# led_driver_v1_1.net
KiCad netlist of a schematic drawn in EAGLE
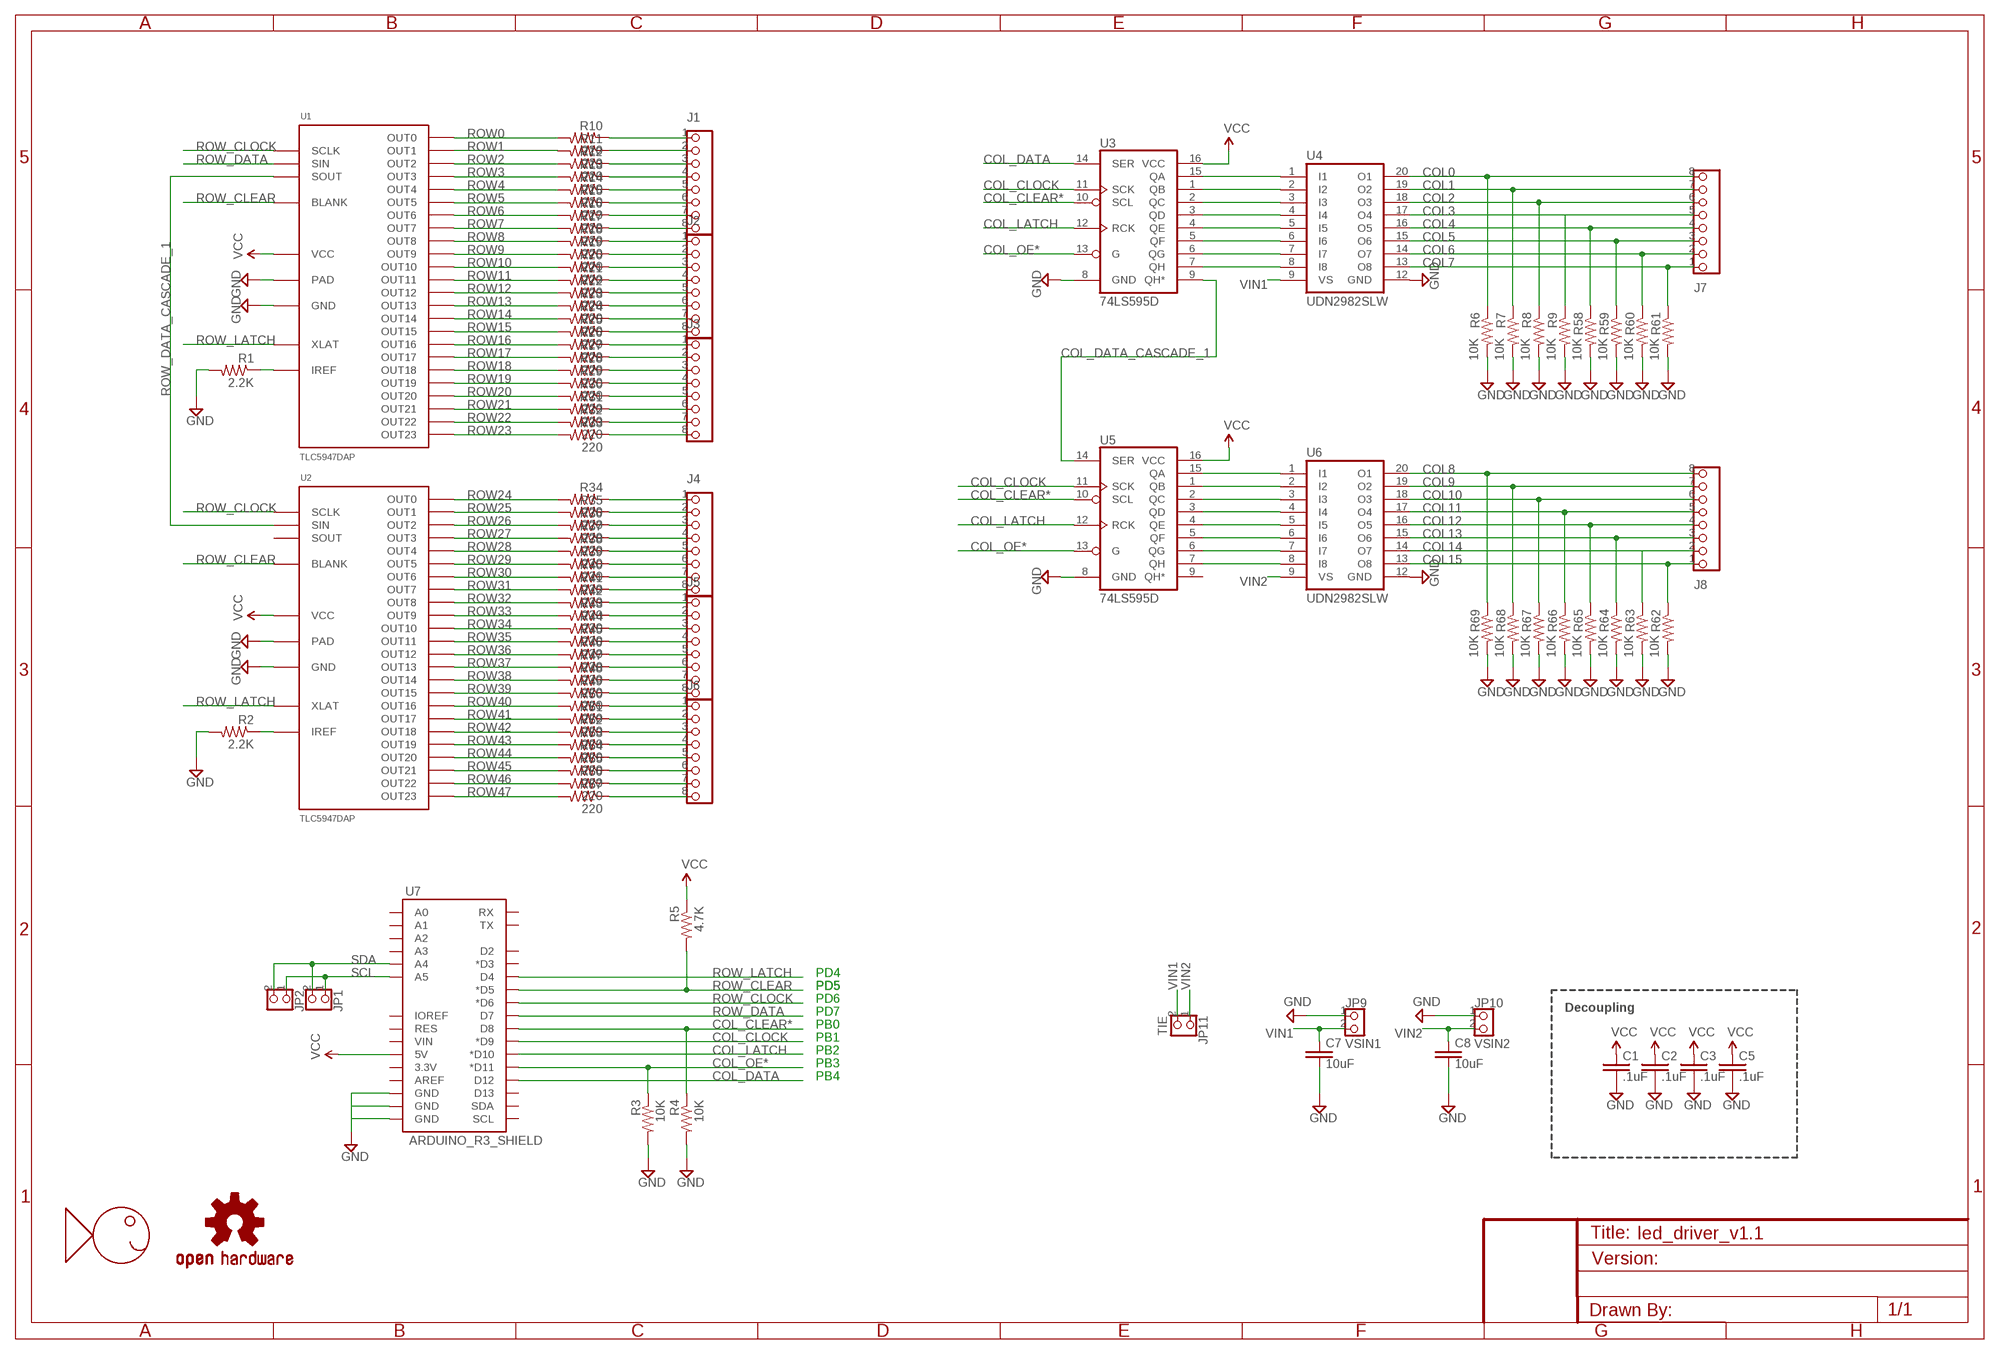
[diagram p0: schematic, sheet 1]

(export (version "E")
  (design (tool "Eeschema 10.0.6"))
  (components
    (comp (ref "C1")
      (value ".1uF")
      (footprint "eagle-import:C0603")
      (libsource (lib "eagle-import") (part "CAPACITORC0603"))
    )
    (comp (ref "C2")
      (value ".1uF")
      (footprint "eagle-import:C0603")
      (libsource (lib "eagle-import") (part "CAPACITORC0603"))
    )
    (comp (ref "C3")
      (value ".1uF")
      (footprint "eagle-import:C0603")
      (libsource (lib "eagle-import") (part "CAPACITORC0603"))
    )
    (comp (ref "C5")
      (value ".1uF")
      (footprint "eagle-import:C0603")
      (libsource (lib "eagle-import") (part "CAPACITORC0603"))
    )
    (comp (ref "C7")
      (value "10uF")
      (footprint "eagle-import:C0603")
      (libsource (lib "eagle-import") (part "CAPACITORC0603"))
    )
    (comp (ref "C8")
      (value "10uF")
      (footprint "eagle-import:C0603")
      (libsource (lib "eagle-import") (part "CAPACITORC0603"))
    )
    (comp (ref "J1")
      (value "PINHD-1X8")
      (footprint "eagle-import:1X08")
      (libsource (lib "eagle-import") (part "PINHD-1X8"))
    )
    (comp (ref "J2")
      (value "PINHD-1X8")
      (footprint "eagle-import:1X08")
      (libsource (lib "eagle-import") (part "PINHD-1X8"))
    )
    (comp (ref "J3")
      (value "PINHD-1X8")
      (footprint "eagle-import:1X08")
      (libsource (lib "eagle-import") (part "PINHD-1X8"))
    )
    (comp (ref "J4")
      (value "PINHD-1X8")
      (footprint "eagle-import:1X08")
      (libsource (lib "eagle-import") (part "PINHD-1X8"))
    )
    (comp (ref "J5")
      (value "PINHD-1X8")
      (footprint "eagle-import:1X08")
      (libsource (lib "eagle-import") (part "PINHD-1X8"))
    )
    (comp (ref "J6")
      (value "PINHD-1X8")
      (footprint "eagle-import:1X08")
      (libsource (lib "eagle-import") (part "PINHD-1X8"))
    )
    (comp (ref "J7")
      (value "PINHD-1X8")
      (footprint "eagle-import:1X08")
      (libsource (lib "eagle-import") (part "PINHD-1X8"))
    )
    (comp (ref "J8")
      (value "PINHD-1X8")
      (footprint "eagle-import:1X08")
      (libsource (lib "eagle-import") (part "PINHD-1X8"))
    )
    (comp (ref "JP1")
      (value "PINHD-1X2")
      (footprint "eagle-import:1X02")
      (libsource (lib "eagle-import") (part "PINHD-1X2"))
    )
    (comp (ref "JP2")
      (value "PINHD-1X2")
      (footprint "eagle-import:1X02")
      (libsource (lib "eagle-import") (part "PINHD-1X2"))
    )
    (comp (ref "JP9")
      (value "VSIN1")
      (footprint "eagle-import:1X02")
      (libsource (lib "eagle-import") (part "PINHD-1X2"))
    )
    (comp (ref "JP10")
      (value "VSIN2")
      (footprint "eagle-import:1X02")
      (libsource (lib "eagle-import") (part "PINHD-1X2"))
    )
    (comp (ref "JP11")
      (value "TIE")
      (footprint "eagle-import:1X02")
      (libsource (lib "eagle-import") (part "PINHD-1X2"))
    )
    (comp (ref "LOGO1")
      (value "OSHW-LOGOS")
      (footprint "eagle-import:OSHW-LOGO-S")
      (libsource (lib "eagle-import") (part "OSHW-LOGOS"))
    )
    (comp (ref "R1")
      (value "2.2K")
      (footprint "eagle-import:0603-RES")
      (libsource (lib "eagle-import") (part "RESISTOR_SMD0603-RES"))
    )
    (comp (ref "R2")
      (value "2.2K")
      (footprint "eagle-import:0603-RES")
      (libsource (lib "eagle-import") (part "RESISTOR_SMD0603-RES"))
    )
    (comp (ref "R3")
      (value "10K")
      (footprint "eagle-import:0603-RES")
      (libsource (lib "eagle-import") (part "RESISTOR_SMD0603-RES"))
    )
    (comp (ref "R4")
      (value "10K")
      (footprint "eagle-import:0603-RES")
      (libsource (lib "eagle-import") (part "RESISTOR_SMD0603-RES"))
    )
    (comp (ref "R5")
      (value "4.7K")
      (footprint "eagle-import:0603-RES")
      (libsource (lib "eagle-import") (part "RESISTOR_SMD0603-RES"))
    )
    (comp (ref "R6")
      (value "10K")
      (footprint "eagle-import:0603-RES")
      (libsource (lib "eagle-import") (part "RESISTOR_SMD0603-RES"))
    )
    (comp (ref "R7")
      (value "10K")
      (footprint "eagle-import:0603-RES")
      (libsource (lib "eagle-import") (part "RESISTOR_SMD0603-RES"))
    )
    (comp (ref "R8")
      (value "10K")
      (footprint "eagle-import:0603-RES")
      (libsource (lib "eagle-import") (part "RESISTOR_SMD0603-RES"))
    )
    (comp (ref "R9")
      (value "10K")
      (footprint "eagle-import:0603-RES")
      (libsource (lib "eagle-import") (part "RESISTOR_SMD0603-RES"))
    )
    (comp (ref "R10")
      (value "220")
      (footprint "eagle-import:0603-RES")
      (libsource (lib "eagle-import") (part "RESISTOR_SMD0603-RES"))
    )
    (comp (ref "R11")
      (value "220")
      (footprint "eagle-import:0603-RES")
      (libsource (lib "eagle-import") (part "RESISTOR_SMD0603-RES"))
    )
    (comp (ref "R12")
      (value "220")
      (footprint "eagle-import:0603-RES")
      (libsource (lib "eagle-import") (part "RESISTOR_SMD0603-RES"))
    )
    (comp (ref "R13")
      (value "220")
      (footprint "eagle-import:0603-RES")
      (libsource (lib "eagle-import") (part "RESISTOR_SMD0603-RES"))
    )
    (comp (ref "R14")
      (value "220")
      (footprint "eagle-import:0603-RES")
      (libsource (lib "eagle-import") (part "RESISTOR_SMD0603-RES"))
    )
    (comp (ref "R15")
      (value "220")
      (footprint "eagle-import:0603-RES")
      (libsource (lib "eagle-import") (part "RESISTOR_SMD0603-RES"))
    )
    (comp (ref "R16")
      (value "220")
      (footprint "eagle-import:0603-RES")
      (libsource (lib "eagle-import") (part "RESISTOR_SMD0603-RES"))
    )
    (comp (ref "R17")
      (value "220")
      (footprint "eagle-import:0603-RES")
      (libsource (lib "eagle-import") (part "RESISTOR_SMD0603-RES"))
    )
    (comp (ref "R18")
      (value "220")
      (footprint "eagle-import:0603-RES")
      (libsource (lib "eagle-import") (part "RESISTOR_SMD0603-RES"))
    )
    (comp (ref "R19")
      (value "220")
      (footprint "eagle-import:0603-RES")
      (libsource (lib "eagle-import") (part "RESISTOR_SMD0603-RES"))
    )
    (comp (ref "R20")
      (value "220")
      (footprint "eagle-import:0603-RES")
      (libsource (lib "eagle-import") (part "RESISTOR_SMD0603-RES"))
    )
    (comp (ref "R21")
      (value "220")
      (footprint "eagle-import:0603-RES")
      (libsource (lib "eagle-import") (part "RESISTOR_SMD0603-RES"))
    )
    (comp (ref "R22")
      (value "220")
      (footprint "eagle-import:0603-RES")
      (libsource (lib "eagle-import") (part "RESISTOR_SMD0603-RES"))
    )
    (comp (ref "R23")
      (value "220")
      (footprint "eagle-import:0603-RES")
      (libsource (lib "eagle-import") (part "RESISTOR_SMD0603-RES"))
    )
    (comp (ref "R24")
      (value "220")
      (footprint "eagle-import:0603-RES")
      (libsource (lib "eagle-import") (part "RESISTOR_SMD0603-RES"))
    )
    (comp (ref "R25")
      (value "220")
      (footprint "eagle-import:0603-RES")
      (libsource (lib "eagle-import") (part "RESISTOR_SMD0603-RES"))
    )
    (comp (ref "R26")
      (value "220")
      (footprint "eagle-import:0603-RES")
      (libsource (lib "eagle-import") (part "RESISTOR_SMD0603-RES"))
    )
    (comp (ref "R27")
      (value "220")
      (footprint "eagle-import:0603-RES")
      (libsource (lib "eagle-import") (part "RESISTOR_SMD0603-RES"))
    )
    (comp (ref "R28")
      (value "220")
      (footprint "eagle-import:0603-RES")
      (libsource (lib "eagle-import") (part "RESISTOR_SMD0603-RES"))
    )
    (comp (ref "R29")
      (value "220")
      (footprint "eagle-import:0603-RES")
      (libsource (lib "eagle-import") (part "RESISTOR_SMD0603-RES"))
    )
    (comp (ref "R30")
      (value "220")
      (footprint "eagle-import:0603-RES")
      (libsource (lib "eagle-import") (part "RESISTOR_SMD0603-RES"))
    )
    (comp (ref "R31")
      (value "220")
      (footprint "eagle-import:0603-RES")
      (libsource (lib "eagle-import") (part "RESISTOR_SMD0603-RES"))
    )
    (comp (ref "R32")
      (value "220")
      (footprint "eagle-import:0603-RES")
      (libsource (lib "eagle-import") (part "RESISTOR_SMD0603-RES"))
    )
    (comp (ref "R33")
      (value "220")
      (footprint "eagle-import:0603-RES")
      (libsource (lib "eagle-import") (part "RESISTOR_SMD0603-RES"))
    )
    (comp (ref "R34")
      (value "220")
      (footprint "eagle-import:0603-RES")
      (libsource (lib "eagle-import") (part "RESISTOR_SMD0603-RES"))
    )
    (comp (ref "R35")
      (value "220")
      (footprint "eagle-import:0603-RES")
      (libsource (lib "eagle-import") (part "RESISTOR_SMD0603-RES"))
    )
    (comp (ref "R36")
      (value "220")
      (footprint "eagle-import:0603-RES")
      (libsource (lib "eagle-import") (part "RESISTOR_SMD0603-RES"))
    )
    (comp (ref "R37")
      (value "220")
      (footprint "eagle-import:0603-RES")
      (libsource (lib "eagle-import") (part "RESISTOR_SMD0603-RES"))
    )
    (comp (ref "R38")
      (value "220")
      (footprint "eagle-import:0603-RES")
      (libsource (lib "eagle-import") (part "RESISTOR_SMD0603-RES"))
    )
    (comp (ref "R39")
      (value "220")
      (footprint "eagle-import:0603-RES")
      (libsource (lib "eagle-import") (part "RESISTOR_SMD0603-RES"))
    )
    (comp (ref "R40")
      (value "220")
      (footprint "eagle-import:0603-RES")
      (libsource (lib "eagle-import") (part "RESISTOR_SMD0603-RES"))
    )
    (comp (ref "R41")
      (value "220")
      (footprint "eagle-import:0603-RES")
      (libsource (lib "eagle-import") (part "RESISTOR_SMD0603-RES"))
    )
    (comp (ref "R42")
      (value "220")
      (footprint "eagle-import:0603-RES")
      (libsource (lib "eagle-import") (part "RESISTOR_SMD0603-RES"))
    )
    (comp (ref "R43")
      (value "220")
      (footprint "eagle-import:0603-RES")
      (libsource (lib "eagle-import") (part "RESISTOR_SMD0603-RES"))
    )
    (comp (ref "R44")
      (value "220")
      (footprint "eagle-import:0603-RES")
      (libsource (lib "eagle-import") (part "RESISTOR_SMD0603-RES"))
    )
    (comp (ref "R45")
      (value "220")
      (footprint "eagle-import:0603-RES")
      (libsource (lib "eagle-import") (part "RESISTOR_SMD0603-RES"))
    )
    (comp (ref "R46")
      (value "220")
      (footprint "eagle-import:0603-RES")
      (libsource (lib "eagle-import") (part "RESISTOR_SMD0603-RES"))
    )
    (comp (ref "R47")
      (value "220")
      (footprint "eagle-import:0603-RES")
      (libsource (lib "eagle-import") (part "RESISTOR_SMD0603-RES"))
    )
    (comp (ref "R48")
      (value "220")
      (footprint "eagle-import:0603-RES")
      (libsource (lib "eagle-import") (part "RESISTOR_SMD0603-RES"))
    )
    (comp (ref "R49")
      (value "220")
      (footprint "eagle-import:0603-RES")
      (libsource (lib "eagle-import") (part "RESISTOR_SMD0603-RES"))
    )
    (comp (ref "R50")
      (value "220")
      (footprint "eagle-import:0603-RES")
      (libsource (lib "eagle-import") (part "RESISTOR_SMD0603-RES"))
    )
    (comp (ref "R51")
      (value "220")
      (footprint "eagle-import:0603-RES")
      (libsource (lib "eagle-import") (part "RESISTOR_SMD0603-RES"))
    )
    (comp (ref "R52")
      (value "220")
      (footprint "eagle-import:0603-RES")
      (libsource (lib "eagle-import") (part "RESISTOR_SMD0603-RES"))
    )
    (comp (ref "R53")
      (value "220")
      (footprint "eagle-import:0603-RES")
      (libsource (lib "eagle-import") (part "RESISTOR_SMD0603-RES"))
    )
    (comp (ref "R54")
      (value "220")
      (footprint "eagle-import:0603-RES")
      (libsource (lib "eagle-import") (part "RESISTOR_SMD0603-RES"))
    )
    (comp (ref "R55")
      (value "220")
      (footprint "eagle-import:0603-RES")
      (libsource (lib "eagle-import") (part "RESISTOR_SMD0603-RES"))
    )
    (comp (ref "R56")
      (value "220")
      (footprint "eagle-import:0603-RES")
      (libsource (lib "eagle-import") (part "RESISTOR_SMD0603-RES"))
    )
    (comp (ref "R57")
      (value "220")
      (footprint "eagle-import:0603-RES")
      (libsource (lib "eagle-import") (part "RESISTOR_SMD0603-RES"))
    )
    (comp (ref "R58")
      (value "10K")
      (footprint "eagle-import:0603-RES")
      (libsource (lib "eagle-import") (part "RESISTOR_SMD0603-RES"))
    )
    (comp (ref "R59")
      (value "10K")
      (footprint "eagle-import:0603-RES")
      (libsource (lib "eagle-import") (part "RESISTOR_SMD0603-RES"))
    )
    (comp (ref "R60")
      (value "10K")
      (footprint "eagle-import:0603-RES")
      (libsource (lib "eagle-import") (part "RESISTOR_SMD0603-RES"))
    )
    (comp (ref "R61")
      (value "10K")
      (footprint "eagle-import:0603-RES")
      (libsource (lib "eagle-import") (part "RESISTOR_SMD0603-RES"))
    )
    (comp (ref "R62")
      (value "10K")
      (footprint "eagle-import:0603-RES")
      (libsource (lib "eagle-import") (part "RESISTOR_SMD0603-RES"))
    )
    (comp (ref "R63")
      (value "10K")
      (footprint "eagle-import:0603-RES")
      (libsource (lib "eagle-import") (part "RESISTOR_SMD0603-RES"))
    )
    (comp (ref "R64")
      (value "10K")
      (footprint "eagle-import:0603-RES")
      (libsource (lib "eagle-import") (part "RESISTOR_SMD0603-RES"))
    )
    (comp (ref "R65")
      (value "10K")
      (footprint "eagle-import:0603-RES")
      (libsource (lib "eagle-import") (part "RESISTOR_SMD0603-RES"))
    )
    (comp (ref "R66")
      (value "10K")
      (footprint "eagle-import:0603-RES")
      (libsource (lib "eagle-import") (part "RESISTOR_SMD0603-RES"))
    )
    (comp (ref "R67")
      (value "10K")
      (footprint "eagle-import:0603-RES")
      (libsource (lib "eagle-import") (part "RESISTOR_SMD0603-RES"))
    )
    (comp (ref "R68")
      (value "10K")
      (footprint "eagle-import:0603-RES")
      (libsource (lib "eagle-import") (part "RESISTOR_SMD0603-RES"))
    )
    (comp (ref "R69")
      (value "10K")
      (footprint "eagle-import:0603-RES")
      (libsource (lib "eagle-import") (part "RESISTOR_SMD0603-RES"))
    )
    (comp (ref "U$1")
      (value "FHI_LOGO")
      (footprint "eagle-import:FHI_LOGO")
      (libsource (lib "eagle-import") (part "FHI_LOGO"))
    )
    (comp (ref "U1")
      (value "TLC5947DAP")
      (footprint "eagle-import:HTSSOP32DAP")
      (libsource (lib "eagle-import") (part "TLC5947DAP"))
    )
    (comp (ref "U2")
      (value "TLC5947DAP")
      (footprint "eagle-import:HTSSOP32DAP")
      (libsource (lib "eagle-import") (part "TLC5947DAP"))
    )
    (comp (ref "U3")
      (value "74LS595D")
      (footprint "eagle-import:SO16")
      (libsource (lib "eagle-import") (part "74595DLS"))
    )
    (comp (ref "U4")
      (value "UDN2982SLW")
      (footprint "eagle-import:SO20W")
      (libsource (lib "eagle-import") (part "UDN298SLW2"))
    )
    (comp (ref "U5")
      (value "74LS595D")
      (footprint "eagle-import:SO16")
      (libsource (lib "eagle-import") (part "74595DLS"))
    )
    (comp (ref "U6")
      (value "UDN2982SLW")
      (footprint "eagle-import:SO20W")
      (libsource (lib "eagle-import") (part "UDN298SLW2"))
    )
    (comp (ref "U7")
      (value "ARDUINO_R3_SHIELD")
      (footprint "eagle-import:UNO_R3_SHIELD")
      (libsource (lib "eagle-import") (part "ARDUINO_R3_SHIELD"))
    )
  )
  (nets
    (net (code "1") (name "/COL0") (class "Default")
      (node (ref "J7") (pin "8") (pinfunction "8_8") (pintype "passive"))
      (node (ref "R6") (pin "1") (pinfunction "1_1") (pintype "passive"))
      (node (ref "U4") (pin "20") (pinfunction "O1_20") (pintype "open_collector"))
    )
    (net (code "2") (name "/COL1") (class "Default")
      (node (ref "J7") (pin "7") (pinfunction "7_7") (pintype "passive"))
      (node (ref "R7") (pin "1") (pinfunction "1_1") (pintype "passive"))
      (node (ref "U4") (pin "19") (pinfunction "O2_19") (pintype "open_collector"))
    )
    (net (code "3") (name "/COL2") (class "Default")
      (node (ref "J7") (pin "6") (pinfunction "6_6") (pintype "passive"))
      (node (ref "R8") (pin "1") (pinfunction "1_1") (pintype "passive"))
      (node (ref "U4") (pin "18") (pinfunction "O3_18") (pintype "open_collector"))
    )
    (net (code "4") (name "/COL3") (class "Default")
      (node (ref "J7") (pin "5") (pinfunction "5_5") (pintype "passive"))
      (node (ref "R9") (pin "1") (pinfunction "1_1") (pintype "passive"))
      (node (ref "U4") (pin "17") (pinfunction "O4_17") (pintype "open_collector"))
    )
    (net (code "5") (name "/COL4") (class "Default")
      (node (ref "J7") (pin "4") (pinfunction "4_4") (pintype "passive"))
      (node (ref "R58") (pin "1") (pinfunction "1_1") (pintype "passive"))
      (node (ref "U4") (pin "16") (pinfunction "O5_16") (pintype "open_collector"))
    )
    (net (code "6") (name "/COL5") (class "Default")
      (node (ref "J7") (pin "3") (pinfunction "3_3") (pintype "passive"))
      (node (ref "R59") (pin "1") (pinfunction "1_1") (pintype "passive"))
      (node (ref "U4") (pin "15") (pinfunction "O6_15") (pintype "open_collector"))
    )
    (net (code "7") (name "/COL6") (class "Default")
      (node (ref "J7") (pin "2") (pinfunction "2_2") (pintype "passive"))
      (node (ref "R60") (pin "1") (pinfunction "1_1") (pintype "passive"))
      (node (ref "U4") (pin "14") (pinfunction "O7_14") (pintype "open_collector"))
    )
    (net (code "8") (name "/COL7") (class "Default")
      (node (ref "J7") (pin "1") (pinfunction "1_1") (pintype "passive"))
      (node (ref "R61") (pin "1") (pinfunction "1_1") (pintype "passive"))
      (node (ref "U4") (pin "13") (pinfunction "O8_13") (pintype "open_collector"))
    )
    (net (code "9") (name "/COL8") (class "Default")
      (node (ref "J8") (pin "8") (pinfunction "8_8") (pintype "passive"))
      (node (ref "R69") (pin "1") (pinfunction "1_1") (pintype "passive"))
      (node (ref "U6") (pin "20") (pinfunction "O1_20") (pintype "open_collector"))
    )
    (net (code "10") (name "/COL9") (class "Default")
      (node (ref "J8") (pin "7") (pinfunction "7_7") (pintype "passive"))
      (node (ref "R68") (pin "1") (pinfunction "1_1") (pintype "passive"))
      (node (ref "U6") (pin "19") (pinfunction "O2_19") (pintype "open_collector"))
    )
    (net (code "11") (name "/COL10") (class "Default")
      (node (ref "J8") (pin "6") (pinfunction "6_6") (pintype "passive"))
      (node (ref "R67") (pin "1") (pinfunction "1_1") (pintype "passive"))
      (node (ref "U6") (pin "18") (pinfunction "O3_18") (pintype "open_collector"))
    )
    (net (code "12") (name "/COL11") (class "Default")
      (node (ref "J8") (pin "5") (pinfunction "5_5") (pintype "passive"))
      (node (ref "R66") (pin "1") (pinfunction "1_1") (pintype "passive"))
      (node (ref "U6") (pin "17") (pinfunction "O4_17") (pintype "open_collector"))
    )
    (net (code "13") (name "/COL12") (class "Default")
      (node (ref "J8") (pin "4") (pinfunction "4_4") (pintype "passive"))
      (node (ref "R65") (pin "1") (pinfunction "1_1") (pintype "passive"))
      (node (ref "U6") (pin "16") (pinfunction "O5_16") (pintype "open_collector"))
    )
    (net (code "14") (name "/COL13") (class "Default")
      (node (ref "J8") (pin "3") (pinfunction "3_3") (pintype "passive"))
      (node (ref "R64") (pin "1") (pinfunction "1_1") (pintype "passive"))
      (node (ref "U6") (pin "15") (pinfunction "O6_15") (pintype "open_collector"))
    )
    (net (code "15") (name "/COL14") (class "Default")
      (node (ref "J8") (pin "2") (pinfunction "2_2") (pintype "passive"))
      (node (ref "R63") (pin "1") (pinfunction "1_1") (pintype "passive"))
      (node (ref "U6") (pin "14") (pinfunction "O7_14") (pintype "open_collector"))
    )
    (net (code "16") (name "/COL15") (class "Default")
      (node (ref "J8") (pin "1") (pinfunction "1_1") (pintype "passive"))
      (node (ref "R62") (pin "1") (pinfunction "1_1") (pintype "passive"))
      (node (ref "U6") (pin "13") (pinfunction "O8_13") (pintype "open_collector"))
    )
    (net (code "17") (name "/COL_CLEAR*") (class "Default")
      (node (ref "R4") (pin "1") (pinfunction "1_1") (pintype "passive"))
      (node (ref "U3") (pin "10") (pinfunction "SCL_10") (pintype "input"))
      (node (ref "U5") (pin "10") (pinfunction "SCL_10") (pintype "input"))
      (node (ref "U7") (pin "D8") (pinfunction "D8_D8") (pintype "bidirectional"))
    )
    (net (code "18") (name "/COL_CLOCK") (class "Default")
      (node (ref "U3") (pin "11") (pinfunction "SCK_11") (pintype "input"))
      (node (ref "U5") (pin "11") (pinfunction "SCK_11") (pintype "input"))
      (node (ref "U7") (pin "D9") (pinfunction "*D9_D9") (pintype "bidirectional"))
    )
    (net (code "19") (name "/COL_DATA") (class "Default")
      (node (ref "U3") (pin "14") (pinfunction "SER_14") (pintype "input"))
      (node (ref "U7") (pin "D12") (pinfunction "D12_D12") (pintype "bidirectional"))
    )
    (net (code "20") (name "/COL_DATA_CASCADE_1") (class "Default")
      (node (ref "U3") (pin "9") (pinfunction "QH*_9") (pintype "tri_state"))
      (node (ref "U5") (pin "14") (pinfunction "SER_14") (pintype "input"))
    )
    (net (code "21") (name "/COL_LATCH") (class "Default")
      (node (ref "U3") (pin "12") (pinfunction "RCK_12") (pintype "input"))
      (node (ref "U5") (pin "12") (pinfunction "RCK_12") (pintype "input"))
      (node (ref "U7") (pin "D10") (pinfunction "*D10_D10") (pintype "bidirectional"))
    )
    (net (code "22") (name "/COL_OE*") (class "Default")
      (node (ref "R3") (pin "1") (pinfunction "1_1") (pintype "passive"))
      (node (ref "U3") (pin "13") (pinfunction "G_13") (pintype "input"))
      (node (ref "U5") (pin "13") (pinfunction "G_13") (pintype "input"))
      (node (ref "U7") (pin "D11") (pinfunction "*D11_D11") (pintype "bidirectional"))
    )
    (net (code "23") (name "/ROW0") (class "Default")
      (node (ref "R10") (pin "2") (pinfunction "2_2") (pintype "passive"))
      (node (ref "U1") (pin "5") (pinfunction "OUT0_5") (pintype "bidirectional"))
    )
    (net (code "24") (name "/ROW1") (class "Default")
      (node (ref "R11") (pin "2") (pinfunction "2_2") (pintype "passive"))
      (node (ref "U1") (pin "6") (pinfunction "OUT1_6") (pintype "bidirectional"))
    )
    (net (code "25") (name "/ROW2") (class "Default")
      (node (ref "R12") (pin "2") (pinfunction "2_2") (pintype "passive"))
      (node (ref "U1") (pin "7") (pinfunction "OUT2_7") (pintype "bidirectional"))
    )
    (net (code "26") (name "/ROW3") (class "Default")
      (node (ref "R13") (pin "2") (pinfunction "2_2") (pintype "passive"))
      (node (ref "U1") (pin "8") (pinfunction "OUT3_8") (pintype "bidirectional"))
    )
    (net (code "27") (name "/ROW4") (class "Default")
      (node (ref "R14") (pin "2") (pinfunction "2_2") (pintype "passive"))
      (node (ref "U1") (pin "9") (pinfunction "OUT4_9") (pintype "bidirectional"))
    )
    (net (code "28") (name "/ROW5") (class "Default")
      (node (ref "R15") (pin "2") (pinfunction "2_2") (pintype "passive"))
      (node (ref "U1") (pin "10") (pinfunction "OUT5_10") (pintype "bidirectional"))
    )
    (net (code "29") (name "/ROW6") (class "Default")
      (node (ref "R16") (pin "2") (pinfunction "2_2") (pintype "passive"))
      (node (ref "U1") (pin "11") (pinfunction "OUT6_11") (pintype "bidirectional"))
    )
    (net (code "30") (name "/ROW7") (class "Default")
      (node (ref "R17") (pin "2") (pinfunction "2_2") (pintype "passive"))
      (node (ref "U1") (pin "12") (pinfunction "OUT7_12") (pintype "bidirectional"))
    )
    (net (code "31") (name "/ROW8") (class "Default")
      (node (ref "R18") (pin "2") (pinfunction "2_2") (pintype "passive"))
      (node (ref "U1") (pin "13") (pinfunction "OUT8_13") (pintype "bidirectional"))
    )
    (net (code "32") (name "/ROW9") (class "Default")
      (node (ref "R19") (pin "2") (pinfunction "2_2") (pintype "passive"))
      (node (ref "U1") (pin "14") (pinfunction "OUT9_14") (pintype "bidirectional"))
    )
    (net (code "33") (name "/ROW10") (class "Default")
      (node (ref "R20") (pin "2") (pinfunction "2_2") (pintype "passive"))
      (node (ref "U1") (pin "15") (pinfunction "OUT10_15") (pintype "bidirectional"))
    )
    (net (code "34") (name "/ROW11") (class "Default")
      (node (ref "R21") (pin "2") (pinfunction "2_2") (pintype "passive"))
      (node (ref "U1") (pin "16") (pinfunction "OUT11_16") (pintype "bidirectional"))
    )
    (net (code "35") (name "/ROW12") (class "Default")
      (node (ref "R22") (pin "2") (pinfunction "2_2") (pintype "passive"))
      (node (ref "U1") (pin "17") (pinfunction "OUT12_17") (pintype "bidirectional"))
    )
    (net (code "36") (name "/ROW13") (class "Default")
      (node (ref "R23") (pin "2") (pinfunction "2_2") (pintype "passive"))
      (node (ref "U1") (pin "18") (pinfunction "OUT13_18") (pintype "bidirectional"))
    )
    (net (code "37") (name "/ROW14") (class "Default")
      (node (ref "R24") (pin "2") (pinfunction "2_2") (pintype "passive"))
      (node (ref "U1") (pin "19") (pinfunction "OUT14_19") (pintype "bidirectional"))
    )
    (net (code "38") (name "/ROW15") (class "Default")
      (node (ref "R25") (pin "2") (pinfunction "2_2") (pintype "passive"))
      (node (ref "U1") (pin "20") (pinfunction "OUT15_20") (pintype "bidirectional"))
    )
    (net (code "39") (name "/ROW16") (class "Default")
      (node (ref "R26") (pin "2") (pinfunction "2_2") (pintype "passive"))
      (node (ref "U1") (pin "21") (pinfunction "OUT16_21") (pintype "bidirectional"))
    )
    (net (code "40") (name "/ROW17") (class "Default")
      (node (ref "R27") (pin "2") (pinfunction "2_2") (pintype "passive"))
      (node (ref "U1") (pin "22") (pinfunction "OUT17_22") (pintype "bidirectional"))
    )
    (net (code "41") (name "/ROW18") (class "Default")
      (node (ref "R28") (pin "2") (pinfunction "2_2") (pintype "passive"))
      (node (ref "U1") (pin "23") (pinfunction "OUT18_23") (pintype "bidirectional"))
    )
    (net (code "42") (name "/ROW19") (class "Default")
      (node (ref "R29") (pin "2") (pinfunction "2_2") (pintype "passive"))
      (node (ref "U1") (pin "24") (pinfunction "OUT19_24") (pintype "bidirectional"))
    )
    (net (code "43") (name "/ROW20") (class "Default")
      (node (ref "R30") (pin "2") (pinfunction "2_2") (pintype "passive"))
      (node (ref "U1") (pin "25") (pinfunction "OUT20_25") (pintype "bidirectional"))
    )
    (net (code "44") (name "/ROW21") (class "Default")
      (node (ref "R31") (pin "2") (pinfunction "2_2") (pintype "passive"))
      (node (ref "U1") (pin "26") (pinfunction "OUT21_26") (pintype "bidirectional"))
    )
    (net (code "45") (name "/ROW22") (class "Default")
      (node (ref "R32") (pin "2") (pinfunction "2_2") (pintype "passive"))
      (node (ref "U1") (pin "27") (pinfunction "OUT22_27") (pintype "bidirectional"))
    )
    (net (code "46") (name "/ROW23") (class "Default")
      (node (ref "R33") (pin "2") (pinfunction "2_2") (pintype "passive"))
      (node (ref "U1") (pin "28") (pinfunction "OUT23_28") (pintype "bidirectional"))
    )
    (net (code "47") (name "/ROW24") (class "Default")
      (node (ref "R34") (pin "2") (pinfunction "2_2") (pintype "passive"))
      (node (ref "U2") (pin "5") (pinfunction "OUT0_5") (pintype "bidirectional"))
    )
    (net (code "48") (name "/ROW25") (class "Default")
      (node (ref "R35") (pin "2") (pinfunction "2_2") (pintype "passive"))
      (node (ref "U2") (pin "6") (pinfunction "OUT1_6") (pintype "bidirectional"))
    )
    (net (code "49") (name "/ROW26") (class "Default")
      (node (ref "R36") (pin "2") (pinfunction "2_2") (pintype "passive"))
      (node (ref "U2") (pin "7") (pinfunction "OUT2_7") (pintype "bidirectional"))
    )
    (net (code "50") (name "/ROW27") (class "Default")
      (node (ref "R37") (pin "2") (pinfunction "2_2") (pintype "passive"))
      (node (ref "U2") (pin "8") (pinfunction "OUT3_8") (pintype "bidirectional"))
    )
    (net (code "51") (name "/ROW28") (class "Default")
      (node (ref "R38") (pin "2") (pinfunction "2_2") (pintype "passive"))
      (node (ref "U2") (pin "9") (pinfunction "OUT4_9") (pintype "bidirectional"))
    )
    (net (code "52") (name "/ROW29") (class "Default")
      (node (ref "R39") (pin "2") (pinfunction "2_2") (pintype "passive"))
      (node (ref "U2") (pin "10") (pinfunction "OUT5_10") (pintype "bidirectional"))
    )
    (net (code "53") (name "/ROW30") (class "Default")
      (node (ref "R40") (pin "2") (pinfunction "2_2") (pintype "passive"))
      (node (ref "U2") (pin "11") (pinfunction "OUT6_11") (pintype "bidirectional"))
    )
    (net (code "54") (name "/ROW31") (class "Default")
      (node (ref "R41") (pin "2") (pinfunction "2_2") (pintype "passive"))
      (node (ref "U2") (pin "12") (pinfunction "OUT7_12") (pintype "bidirectional"))
    )
    (net (code "55") (name "/ROW32") (class "Default")
      (node (ref "R42") (pin "2") (pinfunction "2_2") (pintype "passive"))
      (node (ref "U2") (pin "13") (pinfunction "OUT8_13") (pintype "bidirectional"))
    )
    (net (code "56") (name "/ROW33") (class "Default")
      (node (ref "R43") (pin "2") (pinfunction "2_2") (pintype "passive"))
      (node (ref "U2") (pin "14") (pinfunction "OUT9_14") (pintype "bidirectional"))
    )
    (net (code "57") (name "/ROW34") (class "Default")
      (node (ref "R44") (pin "2") (pinfunction "2_2") (pintype "passive"))
      (node (ref "U2") (pin "15") (pinfunction "OUT10_15") (pintype "bidirectional"))
    )
    (net (code "58") (name "/ROW35") (class "Default")
      (node (ref "R45") (pin "2") (pinfunction "2_2") (pintype "passive"))
      (node (ref "U2") (pin "16") (pinfunction "OUT11_16") (pintype "bidirectional"))
    )
    (net (code "59") (name "/ROW36") (class "Default")
      (node (ref "R46") (pin "2") (pinfunction "2_2") (pintype "passive"))
      (node (ref "U2") (pin "17") (pinfunction "OUT12_17") (pintype "bidirectional"))
    )
    (net (code "60") (name "/ROW37") (class "Default")
      (node (ref "R47") (pin "2") (pinfunction "2_2") (pintype "passive"))
      (node (ref "U2") (pin "18") (pinfunction "OUT13_18") (pintype "bidirectional"))
    )
    (net (code "61") (name "/ROW38") (class "Default")
      (node (ref "R48") (pin "2") (pinfunction "2_2") (pintype "passive"))
      (node (ref "U2") (pin "19") (pinfunction "OUT14_19") (pintype "bidirectional"))
    )
    (net (code "62") (name "/ROW39") (class "Default")
      (node (ref "R49") (pin "2") (pinfunction "2_2") (pintype "passive"))
      (node (ref "U2") (pin "20") (pinfunction "OUT15_20") (pintype "bidirectional"))
    )
    (net (code "63") (name "/ROW40") (class "Default")
      (node (ref "R50") (pin "2") (pinfunction "2_2") (pintype "passive"))
      (node (ref "U2") (pin "21") (pinfunction "OUT16_21") (pintype "bidirectional"))
    )
    (net (code "64") (name "/ROW41") (class "Default")
      (node (ref "R51") (pin "2") (pinfunction "2_2") (pintype "passive"))
      (node (ref "U2") (pin "22") (pinfunction "OUT17_22") (pintype "bidirectional"))
    )
    (net (code "65") (name "/ROW42") (class "Default")
      (node (ref "R52") (pin "2") (pinfunction "2_2") (pintype "passive"))
      (node (ref "U2") (pin "23") (pinfunction "OUT18_23") (pintype "bidirectional"))
    )
    (net (code "66") (name "/ROW43") (class "Default")
      (node (ref "R53") (pin "2") (pinfunction "2_2") (pintype "passive"))
      (node (ref "U2") (pin "24") (pinfunction "OUT19_24") (pintype "bidirectional"))
    )
    (net (code "67") (name "/ROW44") (class "Default")
      (node (ref "R54") (pin "2") (pinfunction "2_2") (pintype "passive"))
      (node (ref "U2") (pin "25") (pinfunction "OUT20_25") (pintype "bidirectional"))
    )
    (net (code "68") (name "/ROW45") (class "Default")
      (node (ref "R55") (pin "2") (pinfunction "2_2") (pintype "passive"))
      (node (ref "U2") (pin "26") (pinfunction "OUT21_26") (pintype "bidirectional"))
    )
    (net (code "69") (name "/ROW46") (class "Default")
      (node (ref "R56") (pin "2") (pinfunction "2_2") (pintype "passive"))
      (node (ref "U2") (pin "27") (pinfunction "OUT22_27") (pintype "bidirectional"))
    )
    (net (code "70") (name "/ROW47") (class "Default")
      (node (ref "R57") (pin "2") (pinfunction "2_2") (pintype "passive"))
      (node (ref "U2") (pin "28") (pinfunction "OUT23_28") (pintype "bidirectional"))
    )
    (net (code "71") (name "/ROW_CLEAR") (class "Default")
      (node (ref "R5") (pin "2") (pinfunction "2_2") (pintype "passive"))
      (node (ref "U1") (pin "2") (pinfunction "BLANK_2") (pintype "bidirectional"))
      (node (ref "U2") (pin "2") (pinfunction "BLANK_2") (pintype "bidirectional"))
      (node (ref "U7") (pin "D5") (pinfunction "*D5_D5") (pintype "bidirectional"))
    )
    (net (code "72") (name "/ROW_CLOCK") (class "Default")
      (node (ref "U1") (pin "3") (pinfunction "SCLK_3") (pintype "bidirectional"))
      (node (ref "U2") (pin "3") (pinfunction "SCLK_3") (pintype "bidirectional"))
      (node (ref "U7") (pin "D6") (pinfunction "*D6_D6") (pintype "bidirectional"))
    )
    (net (code "73") (name "/ROW_DATA") (class "Default")
      (node (ref "U1") (pin "4") (pinfunction "SIN_4") (pintype "bidirectional"))
      (node (ref "U7") (pin "D7") (pinfunction "D7_D7") (pintype "bidirectional"))
    )
    (net (code "74") (name "/ROW_DATA_CASCADE_1") (class "Default")
      (node (ref "U1") (pin "29") (pinfunction "SOUT_29") (pintype "bidirectional"))
      (node (ref "U2") (pin "4") (pinfunction "SIN_4") (pintype "bidirectional"))
    )
    (net (code "75") (name "/ROW_LATCH") (class "Default")
      (node (ref "U1") (pin "30") (pinfunction "XLAT_30") (pintype "bidirectional"))
      (node (ref "U2") (pin "30") (pinfunction "XLAT_30") (pintype "bidirectional"))
      (node (ref "U7") (pin "D4") (pinfunction "D4_D4") (pintype "bidirectional"))
    )
    (net (code "76") (name "/SCL") (class "Default")
      (node (ref "JP1") (pin "1") (pinfunction "1_1") (pintype "passive"))
      (node (ref "JP2") (pin "1") (pinfunction "1_1") (pintype "passive"))
      (node (ref "U7") (pin "A5") (pinfunction "A5_A5") (pintype "bidirectional"))
    )
    (net (code "77") (name "/SDA") (class "Default")
      (node (ref "JP1") (pin "2") (pinfunction "2_2") (pintype "passive"))
      (node (ref "JP2") (pin "2") (pinfunction "2_2") (pintype "passive"))
      (node (ref "U7") (pin "A4") (pinfunction "A4_A4") (pintype "bidirectional"))
    )
    (net (code "78") (name "/VIN1") (class "Default")
      (node (ref "C7") (pin "1") (pinfunction "1_1") (pintype "passive"))
      (node (ref "JP11") (pin "2") (pinfunction "2_2") (pintype "passive"))
      (node (ref "JP9") (pin "2") (pinfunction "2_2") (pintype "passive"))
      (node (ref "U4") (pin "9") (pinfunction "VS_9") (pintype "passive"))
    )
    (net (code "79") (name "/VIN2") (class "Default")
      (node (ref "C8") (pin "1") (pinfunction "1_1") (pintype "passive"))
      (node (ref "JP10") (pin "2") (pinfunction "2_2") (pintype "passive"))
      (node (ref "JP11") (pin "1") (pinfunction "1_1") (pintype "passive"))
      (node (ref "U6") (pin "9") (pinfunction "VS_9") (pintype "passive"))
    )
    (net (code "80") (name "GND") (class "Default")
      (node (ref "C1") (pin "2") (pinfunction "2_2") (pintype "passive"))
      (node (ref "C2") (pin "2") (pinfunction "2_2") (pintype "passive"))
      (node (ref "C3") (pin "2") (pinfunction "2_2") (pintype "passive"))
      (node (ref "C5") (pin "2") (pinfunction "2_2") (pintype "passive"))
      (node (ref "C7") (pin "2") (pinfunction "2_2") (pintype "passive"))
      (node (ref "C8") (pin "2") (pinfunction "2_2") (pintype "passive"))
      (node (ref "JP10") (pin "1") (pinfunction "1_1") (pintype "passive"))
      (node (ref "JP9") (pin "1") (pinfunction "1_1") (pintype "passive"))
      (node (ref "R1") (pin "2") (pinfunction "2_2") (pintype "passive"))
      (node (ref "R2") (pin "2") (pinfunction "2_2") (pintype "passive"))
      (node (ref "R3") (pin "2") (pinfunction "2_2") (pintype "passive"))
      (node (ref "R4") (pin "2") (pinfunction "2_2") (pintype "passive"))
      (node (ref "R58") (pin "2") (pinfunction "2_2") (pintype "passive"))
      (node (ref "R59") (pin "2") (pinfunction "2_2") (pintype "passive"))
      (node (ref "R6") (pin "2") (pinfunction "2_2") (pintype "passive"))
      (node (ref "R60") (pin "2") (pinfunction "2_2") (pintype "passive"))
      (node (ref "R61") (pin "2") (pinfunction "2_2") (pintype "passive"))
      (node (ref "R62") (pin "2") (pinfunction "2_2") (pintype "passive"))
      (node (ref "R63") (pin "2") (pinfunction "2_2") (pintype "passive"))
      (node (ref "R64") (pin "2") (pinfunction "2_2") (pintype "passive"))
      (node (ref "R65") (pin "2") (pinfunction "2_2") (pintype "passive"))
      (node (ref "R66") (pin "2") (pinfunction "2_2") (pintype "passive"))
      (node (ref "R67") (pin "2") (pinfunction "2_2") (pintype "passive"))
      (node (ref "R68") (pin "2") (pinfunction "2_2") (pintype "passive"))
      (node (ref "R69") (pin "2") (pinfunction "2_2") (pintype "passive"))
      (node (ref "R7") (pin "2") (pinfunction "2_2") (pintype "passive"))
      (node (ref "R8") (pin "2") (pinfunction "2_2") (pintype "passive"))
      (node (ref "R9") (pin "2") (pinfunction "2_2") (pintype "passive"))
      (node (ref "U1") (pin "1") (pinfunction "GND_1") (pintype "bidirectional"))
      (node (ref "U1") (pin "EXP") (pinfunction "PAD_EXP") (pintype "bidirectional"))
      (node (ref "U2") (pin "1") (pinfunction "GND_1") (pintype "bidirectional"))
      (node (ref "U2") (pin "EXP") (pinfunction "PAD_EXP") (pintype "bidirectional"))
      (node (ref "U3") (pin "8") (pinfunction "GND_8") (pintype "power_in"))
      (node (ref "U4") (pin "12") (pinfunction "GND_12") (pintype "power_in"))
      (node (ref "U5") (pin "8") (pinfunction "GND_8") (pintype "power_in"))
      (node (ref "U6") (pin "12") (pinfunction "GND_12") (pintype "power_in"))
      (node (ref "U7") (pin "GND@0") (pinfunction "GND_GND@0") (pintype "bidirectional"))
      (node (ref "U7") (pin "GND@1") (pinfunction "GND_GND@1") (pintype "bidirectional"))
      (node (ref "U7") (pin "GND@2") (pinfunction "GND_GND@2") (pintype "bidirectional"))
    )
    (net (code "81") (name "Net-(J1-Pad1)") (class "Default")
      (node (ref "J1") (pin "1") (pinfunction "1_1") (pintype "passive"))
      (node (ref "R10") (pin "1") (pinfunction "1_1") (pintype "passive"))
    )
    (net (code "82") (name "Net-(J1-Pad2)") (class "Default")
      (node (ref "J1") (pin "2") (pinfunction "2_2") (pintype "passive"))
      (node (ref "R11") (pin "1") (pinfunction "1_1") (pintype "passive"))
    )
    (net (code "83") (name "Net-(J1-Pad3)") (class "Default")
      (node (ref "J1") (pin "3") (pinfunction "3_3") (pintype "passive"))
      (node (ref "R12") (pin "1") (pinfunction "1_1") (pintype "passive"))
    )
    (net (code "84") (name "Net-(J1-Pad4)") (class "Default")
      (node (ref "J1") (pin "4") (pinfunction "4_4") (pintype "passive"))
      (node (ref "R13") (pin "1") (pinfunction "1_1") (pintype "passive"))
    )
    (net (code "85") (name "Net-(J1-Pad5)") (class "Default")
      (node (ref "J1") (pin "5") (pinfunction "5_5") (pintype "passive"))
      (node (ref "R14") (pin "1") (pinfunction "1_1") (pintype "passive"))
    )
    (net (code "86") (name "Net-(J1-Pad6)") (class "Default")
      (node (ref "J1") (pin "6") (pinfunction "6_6") (pintype "passive"))
      (node (ref "R15") (pin "1") (pinfunction "1_1") (pintype "passive"))
    )
    (net (code "87") (name "Net-(J1-Pad7)") (class "Default")
      (node (ref "J1") (pin "7") (pinfunction "7_7") (pintype "passive"))
      (node (ref "R16") (pin "1") (pinfunction "1_1") (pintype "passive"))
    )
    (net (code "88") (name "Net-(J1-Pad8)") (class "Default")
      (node (ref "J1") (pin "8") (pinfunction "8_8") (pintype "passive"))
      (node (ref "R17") (pin "1") (pinfunction "1_1") (pintype "passive"))
    )
    (net (code "89") (name "Net-(J2-Pad1)") (class "Default")
      (node (ref "J2") (pin "1") (pinfunction "1_1") (pintype "passive"))
      (node (ref "R18") (pin "1") (pinfunction "1_1") (pintype "passive"))
    )
    (net (code "90") (name "Net-(J2-Pad2)") (class "Default")
      (node (ref "J2") (pin "2") (pinfunction "2_2") (pintype "passive"))
      (node (ref "R19") (pin "1") (pinfunction "1_1") (pintype "passive"))
    )
    (net (code "91") (name "Net-(J2-Pad3)") (class "Default")
      (node (ref "J2") (pin "3") (pinfunction "3_3") (pintype "passive"))
      (node (ref "R20") (pin "1") (pinfunction "1_1") (pintype "passive"))
    )
    (net (code "92") (name "Net-(J2-Pad4)") (class "Default")
      (node (ref "J2") (pin "4") (pinfunction "4_4") (pintype "passive"))
      (node (ref "R21") (pin "1") (pinfunction "1_1") (pintype "passive"))
    )
    (net (code "93") (name "Net-(J2-Pad5)") (class "Default")
      (node (ref "J2") (pin "5") (pinfunction "5_5") (pintype "passive"))
      (node (ref "R22") (pin "1") (pinfunction "1_1") (pintype "passive"))
    )
    (net (code "94") (name "Net-(J2-Pad6)") (class "Default")
      (node (ref "J2") (pin "6") (pinfunction "6_6") (pintype "passive"))
      (node (ref "R23") (pin "1") (pinfunction "1_1") (pintype "passive"))
    )
    (net (code "95") (name "Net-(J2-Pad7)") (class "Default")
      (node (ref "J2") (pin "7") (pinfunction "7_7") (pintype "passive"))
      (node (ref "R24") (pin "1") (pinfunction "1_1") (pintype "passive"))
    )
    (net (code "96") (name "Net-(J2-Pad8)") (class "Default")
      (node (ref "J2") (pin "8") (pinfunction "8_8") (pintype "passive"))
      (node (ref "R25") (pin "1") (pinfunction "1_1") (pintype "passive"))
    )
    (net (code "97") (name "Net-(J3-Pad1)") (class "Default")
      (node (ref "J3") (pin "1") (pinfunction "1_1") (pintype "passive"))
      (node (ref "R26") (pin "1") (pinfunction "1_1") (pintype "passive"))
    )
    (net (code "98") (name "Net-(J3-Pad2)") (class "Default")
      (node (ref "J3") (pin "2") (pinfunction "2_2") (pintype "passive"))
      (node (ref "R27") (pin "1") (pinfunction "1_1") (pintype "passive"))
    )
    (net (code "99") (name "Net-(J3-Pad3)") (class "Default")
      (node (ref "J3") (pin "3") (pinfunction "3_3") (pintype "passive"))
      (node (ref "R28") (pin "1") (pinfunction "1_1") (pintype "passive"))
    )
    (net (code "100") (name "Net-(J3-Pad4)") (class "Default")
      (node (ref "J3") (pin "4") (pinfunction "4_4") (pintype "passive"))
      (node (ref "R29") (pin "1") (pinfunction "1_1") (pintype "passive"))
    )
    (net (code "101") (name "Net-(J3-Pad5)") (class "Default")
      (node (ref "J3") (pin "5") (pinfunction "5_5") (pintype "passive"))
      (node (ref "R30") (pin "1") (pinfunction "1_1") (pintype "passive"))
    )
    (net (code "102") (name "Net-(J3-Pad6)") (class "Default")
      (node (ref "J3") (pin "6") (pinfunction "6_6") (pintype "passive"))
      (node (ref "R31") (pin "1") (pinfunction "1_1") (pintype "passive"))
    )
    (net (code "103") (name "Net-(J3-Pad7)") (class "Default")
      (node (ref "J3") (pin "7") (pinfunction "7_7") (pintype "passive"))
      (node (ref "R32") (pin "1") (pinfunction "1_1") (pintype "passive"))
    )
    (net (code "104") (name "Net-(J3-Pad8)") (class "Default")
      (node (ref "J3") (pin "8") (pinfunction "8_8") (pintype "passive"))
      (node (ref "R33") (pin "1") (pinfunction "1_1") (pintype "passive"))
    )
    (net (code "105") (name "Net-(J4-Pad1)") (class "Default")
      (node (ref "J4") (pin "1") (pinfunction "1_1") (pintype "passive"))
      (node (ref "R34") (pin "1") (pinfunction "1_1") (pintype "passive"))
    )
    (net (code "106") (name "Net-(J4-Pad2)") (class "Default")
      (node (ref "J4") (pin "2") (pinfunction "2_2") (pintype "passive"))
      (node (ref "R35") (pin "1") (pinfunction "1_1") (pintype "passive"))
    )
    (net (code "107") (name "Net-(J4-Pad3)") (class "Default")
      (node (ref "J4") (pin "3") (pinfunction "3_3") (pintype "passive"))
      (node (ref "R36") (pin "1") (pinfunction "1_1") (pintype "passive"))
    )
    (net (code "108") (name "Net-(J4-Pad4)") (class "Default")
      (node (ref "J4") (pin "4") (pinfunction "4_4") (pintype "passive"))
      (node (ref "R37") (pin "1") (pinfunction "1_1") (pintype "passive"))
    )
    (net (code "109") (name "Net-(J4-Pad5)") (class "Default")
      (node (ref "J4") (pin "5") (pinfunction "5_5") (pintype "passive"))
      (node (ref "R38") (pin "1") (pinfunction "1_1") (pintype "passive"))
    )
    (net (code "110") (name "Net-(J4-Pad6)") (class "Default")
      (node (ref "J4") (pin "6") (pinfunction "6_6") (pintype "passive"))
      (node (ref "R39") (pin "1") (pinfunction "1_1") (pintype "passive"))
    )
    (net (code "111") (name "Net-(J4-Pad7)") (class "Default")
      (node (ref "J4") (pin "7") (pinfunction "7_7") (pintype "passive"))
      (node (ref "R40") (pin "1") (pinfunction "1_1") (pintype "passive"))
    )
    (net (code "112") (name "Net-(J4-Pad8)") (class "Default")
      (node (ref "J4") (pin "8") (pinfunction "8_8") (pintype "passive"))
      (node (ref "R41") (pin "1") (pinfunction "1_1") (pintype "passive"))
    )
    (net (code "113") (name "Net-(J5-Pad1)") (class "Default")
      (node (ref "J5") (pin "1") (pinfunction "1_1") (pintype "passive"))
      (node (ref "R42") (pin "1") (pinfunction "1_1") (pintype "passive"))
    )
    (net (code "114") (name "Net-(J5-Pad2)") (class "Default")
      (node (ref "J5") (pin "2") (pinfunction "2_2") (pintype "passive"))
      (node (ref "R43") (pin "1") (pinfunction "1_1") (pintype "passive"))
    )
    (net (code "115") (name "Net-(J5-Pad3)") (class "Default")
      (node (ref "J5") (pin "3") (pinfunction "3_3") (pintype "passive"))
      (node (ref "R44") (pin "1") (pinfunction "1_1") (pintype "passive"))
    )
    (net (code "116") (name "Net-(J5-Pad4)") (class "Default")
      (node (ref "J5") (pin "4") (pinfunction "4_4") (pintype "passive"))
      (node (ref "R45") (pin "1") (pinfunction "1_1") (pintype "passive"))
    )
    (net (code "117") (name "Net-(J5-Pad5)") (class "Default")
      (node (ref "J5") (pin "5") (pinfunction "5_5") (pintype "passive"))
      (node (ref "R46") (pin "1") (pinfunction "1_1") (pintype "passive"))
    )
    (net (code "118") (name "Net-(J5-Pad6)") (class "Default")
      (node (ref "J5") (pin "6") (pinfunction "6_6") (pintype "passive"))
      (node (ref "R47") (pin "1") (pinfunction "1_1") (pintype "passive"))
    )
    (net (code "119") (name "Net-(J5-Pad7)") (class "Default")
      (node (ref "J5") (pin "7") (pinfunction "7_7") (pintype "passive"))
      (node (ref "R48") (pin "1") (pinfunction "1_1") (pintype "passive"))
    )
    (net (code "120") (name "Net-(J5-Pad8)") (class "Default")
      (node (ref "J5") (pin "8") (pinfunction "8_8") (pintype "passive"))
      (node (ref "R49") (pin "1") (pinfunction "1_1") (pintype "passive"))
    )
    (net (code "121") (name "Net-(J6-Pad1)") (class "Default")
      (node (ref "J6") (pin "1") (pinfunction "1_1") (pintype "passive"))
      (node (ref "R50") (pin "1") (pinfunction "1_1") (pintype "passive"))
    )
    (net (code "122") (name "Net-(J6-Pad2)") (class "Default")
      (node (ref "J6") (pin "2") (pinfunction "2_2") (pintype "passive"))
      (node (ref "R51") (pin "1") (pinfunction "1_1") (pintype "passive"))
    )
    (net (code "123") (name "Net-(J6-Pad3)") (class "Default")
      (node (ref "J6") (pin "3") (pinfunction "3_3") (pintype "passive"))
      (node (ref "R52") (pin "1") (pinfunction "1_1") (pintype "passive"))
    )
    (net (code "124") (name "Net-(J6-Pad4)") (class "Default")
      (node (ref "J6") (pin "4") (pinfunction "4_4") (pintype "passive"))
      (node (ref "R53") (pin "1") (pinfunction "1_1") (pintype "passive"))
    )
    (net (code "125") (name "Net-(J6-Pad5)") (class "Default")
      (node (ref "J6") (pin "5") (pinfunction "5_5") (pintype "passive"))
      (node (ref "R54") (pin "1") (pinfunction "1_1") (pintype "passive"))
    )
    (net (code "126") (name "Net-(J6-Pad6)") (class "Default")
      (node (ref "J6") (pin "6") (pinfunction "6_6") (pintype "passive"))
      (node (ref "R55") (pin "1") (pinfunction "1_1") (pintype "passive"))
    )
    (net (code "127") (name "Net-(J6-Pad7)") (class "Default")
      (node (ref "J6") (pin "7") (pinfunction "7_7") (pintype "passive"))
      (node (ref "R56") (pin "1") (pinfunction "1_1") (pintype "passive"))
    )
    (net (code "128") (name "Net-(J6-Pad8)") (class "Default")
      (node (ref "J6") (pin "8") (pinfunction "8_8") (pintype "passive"))
      (node (ref "R57") (pin "1") (pinfunction "1_1") (pintype "passive"))
    )
    (net (code "129") (name "Net-(U1-IREF)") (class "Default")
      (node (ref "R1") (pin "1") (pinfunction "1_1") (pintype "passive"))
      (node (ref "U1") (pin "31") (pinfunction "IREF_31") (pintype "bidirectional"))
    )
    (net (code "130") (name "Net-(U2-IREF)") (class "Default")
      (node (ref "R2") (pin "1") (pinfunction "1_1") (pintype "passive"))
      (node (ref "U2") (pin "31") (pinfunction "IREF_31") (pintype "bidirectional"))
    )
    (net (code "131") (name "Net-(U3-QA)") (class "Default")
      (node (ref "U3") (pin "15") (pinfunction "QA_15") (pintype "tri_state"))
      (node (ref "U4") (pin "1") (pinfunction "I1_1") (pintype "input"))
    )
    (net (code "132") (name "Net-(U3-QB)") (class "Default")
      (node (ref "U3") (pin "1") (pinfunction "QB_1") (pintype "tri_state"))
      (node (ref "U4") (pin "2") (pinfunction "I2_2") (pintype "input"))
    )
    (net (code "133") (name "Net-(U3-QC)") (class "Default")
      (node (ref "U3") (pin "2") (pinfunction "QC_2") (pintype "tri_state"))
      (node (ref "U4") (pin "3") (pinfunction "I3_3") (pintype "input"))
    )
    (net (code "134") (name "Net-(U3-QD)") (class "Default")
      (node (ref "U3") (pin "3") (pinfunction "QD_3") (pintype "tri_state"))
      (node (ref "U4") (pin "4") (pinfunction "I4_4") (pintype "input"))
    )
    (net (code "135") (name "Net-(U3-QE)") (class "Default")
      (node (ref "U3") (pin "4") (pinfunction "QE_4") (pintype "tri_state"))
      (node (ref "U4") (pin "5") (pinfunction "I5_5") (pintype "input"))
    )
    (net (code "136") (name "Net-(U3-QF)") (class "Default")
      (node (ref "U3") (pin "5") (pinfunction "QF_5") (pintype "tri_state"))
      (node (ref "U4") (pin "6") (pinfunction "I6_6") (pintype "input"))
    )
    (net (code "137") (name "Net-(U3-QG)") (class "Default")
      (node (ref "U3") (pin "6") (pinfunction "QG_6") (pintype "tri_state"))
      (node (ref "U4") (pin "7") (pinfunction "I7_7") (pintype "input"))
    )
    (net (code "138") (name "Net-(U3-QH)") (class "Default")
      (node (ref "U3") (pin "7") (pinfunction "QH_7") (pintype "tri_state"))
      (node (ref "U4") (pin "8") (pinfunction "I8_8") (pintype "input"))
    )
    (net (code "139") (name "Net-(U5-QA)") (class "Default")
      (node (ref "U5") (pin "15") (pinfunction "QA_15") (pintype "tri_state"))
      (node (ref "U6") (pin "1") (pinfunction "I1_1") (pintype "input"))
    )
    (net (code "140") (name "Net-(U5-QB)") (class "Default")
      (node (ref "U5") (pin "1") (pinfunction "QB_1") (pintype "tri_state"))
      (node (ref "U6") (pin "2") (pinfunction "I2_2") (pintype "input"))
    )
    (net (code "141") (name "Net-(U5-QC)") (class "Default")
      (node (ref "U5") (pin "2") (pinfunction "QC_2") (pintype "tri_state"))
      (node (ref "U6") (pin "3") (pinfunction "I3_3") (pintype "input"))
    )
    (net (code "142") (name "Net-(U5-QD)") (class "Default")
      (node (ref "U5") (pin "3") (pinfunction "QD_3") (pintype "tri_state"))
      (node (ref "U6") (pin "4") (pinfunction "I4_4") (pintype "input"))
    )
    (net (code "143") (name "Net-(U5-QE)") (class "Default")
      (node (ref "U5") (pin "4") (pinfunction "QE_4") (pintype "tri_state"))
      (node (ref "U6") (pin "5") (pinfunction "I5_5") (pintype "input"))
    )
    (net (code "144") (name "Net-(U5-QF)") (class "Default")
      (node (ref "U5") (pin "5") (pinfunction "QF_5") (pintype "tri_state"))
      (node (ref "U6") (pin "6") (pinfunction "I6_6") (pintype "input"))
    )
    (net (code "145") (name "Net-(U5-QG)") (class "Default")
      (node (ref "U5") (pin "6") (pinfunction "QG_6") (pintype "tri_state"))
      (node (ref "U6") (pin "7") (pinfunction "I7_7") (pintype "input"))
    )
    (net (code "146") (name "Net-(U5-QH)") (class "Default")
      (node (ref "U5") (pin "7") (pinfunction "QH_7") (pintype "tri_state"))
      (node (ref "U6") (pin "8") (pinfunction "I8_8") (pintype "input"))
    )
    (net (code "147") (name "VCC") (class "Default")
      (node (ref "C1") (pin "1") (pinfunction "1_1") (pintype "passive"))
      (node (ref "C2") (pin "1") (pinfunction "1_1") (pintype "passive"))
      (node (ref "C3") (pin "1") (pinfunction "1_1") (pintype "passive"))
      (node (ref "C5") (pin "1") (pinfunction "1_1") (pintype "passive"))
      (node (ref "R5") (pin "1") (pinfunction "1_1") (pintype "passive"))
      (node (ref "U1") (pin "32") (pinfunction "VCC_32") (pintype "bidirectional"))
      (node (ref "U2") (pin "32") (pinfunction "VCC_32") (pintype "bidirectional"))
      (node (ref "U3") (pin "16") (pinfunction "VCC_16") (pintype "power_in"))
      (node (ref "U5") (pin "16") (pinfunction "VCC_16") (pintype "power_in"))
      (node (ref "U7") (pin "5V") (pinfunction "5V_5V") (pintype "bidirectional"))
    )
    (net (code "148") (name "unconnected-(U2-SOUT-Pad29)") (class "Default")
      (node (ref "U2") (pin "29") (pinfunction "SOUT_29") (pintype "bidirectional"))
    )
    (net (code "149") (name "unconnected-(U5-QH*-Pad9)") (class "Default")
      (node (ref "U5") (pin "9") (pinfunction "QH*_9") (pintype "tri_state"))
    )
    (net (code "150") (name "unconnected-(U7-*D3-PadD3)") (class "Default")
      (node (ref "U7") (pin "D3") (pinfunction "*D3_D3") (pintype "bidirectional"))
    )
    (net (code "151") (name "unconnected-(U7-Pad3.3V)") (class "Default")
      (node (ref "U7") (pin "3.3V") (pinfunction "3.3V_3.3V") (pintype "bidirectional"))
    )
    (net (code "152") (name "unconnected-(U7-PadA0)") (class "Default")
      (node (ref "U7") (pin "A0") (pinfunction "A0_A0") (pintype "bidirectional"))
    )
    (net (code "153") (name "unconnected-(U7-PadA1)") (class "Default")
      (node (ref "U7") (pin "A1") (pinfunction "A1_A1") (pintype "bidirectional"))
    )
    (net (code "154") (name "unconnected-(U7-PadA2)") (class "Default")
      (node (ref "U7") (pin "A2") (pinfunction "A2_A2") (pintype "bidirectional"))
    )
    (net (code "155") (name "unconnected-(U7-PadA3)") (class "Default")
      (node (ref "U7") (pin "A3") (pinfunction "A3_A3") (pintype "bidirectional"))
    )
    (net (code "156") (name "unconnected-(U7-PadAREF)") (class "Default")
      (node (ref "U7") (pin "AREF") (pinfunction "AREF_AREF") (pintype "bidirectional"))
    )
    (net (code "157") (name "unconnected-(U7-PadD2)") (class "Default")
      (node (ref "U7") (pin "D2") (pinfunction "D2_D2") (pintype "bidirectional"))
    )
    (net (code "158") (name "unconnected-(U7-PadD13)") (class "Default")
      (node (ref "U7") (pin "D13") (pinfunction "D13_D13") (pintype "bidirectional"))
    )
    (net (code "159") (name "unconnected-(U7-PadIOREF)") (class "Default")
      (node (ref "U7") (pin "IOREF") (pinfunction "IOREF_IOREF") (pintype "bidirectional"))
    )
    (net (code "160") (name "unconnected-(U7-PadRES)") (class "Default")
      (node (ref "U7") (pin "RES") (pinfunction "RES_RES") (pintype "bidirectional"))
    )
    (net (code "161") (name "unconnected-(U7-PadRX)") (class "Default")
      (node (ref "U7") (pin "RX") (pinfunction "RX_RX") (pintype "bidirectional"))
    )
    (net (code "162") (name "unconnected-(U7-PadSCL)") (class "Default")
      (node (ref "U7") (pin "SCL") (pinfunction "SCL_SCL") (pintype "bidirectional"))
    )
    (net (code "163") (name "unconnected-(U7-PadSDA)") (class "Default")
      (node (ref "U7") (pin "SDA") (pinfunction "SDA_SDA") (pintype "bidirectional"))
    )
    (net (code "164") (name "unconnected-(U7-PadTX)") (class "Default")
      (node (ref "U7") (pin "TX") (pinfunction "TX_TX") (pintype "bidirectional"))
    )
    (net (code "165") (name "unconnected-(U7-PadVIN)") (class "Default")
      (node (ref "U7") (pin "VIN") (pinfunction "VIN_VIN") (pintype "bidirectional"))
    )
  )
)
